# PCF8574T.net
KiCad netlist of a schematic drawn in EAGLE
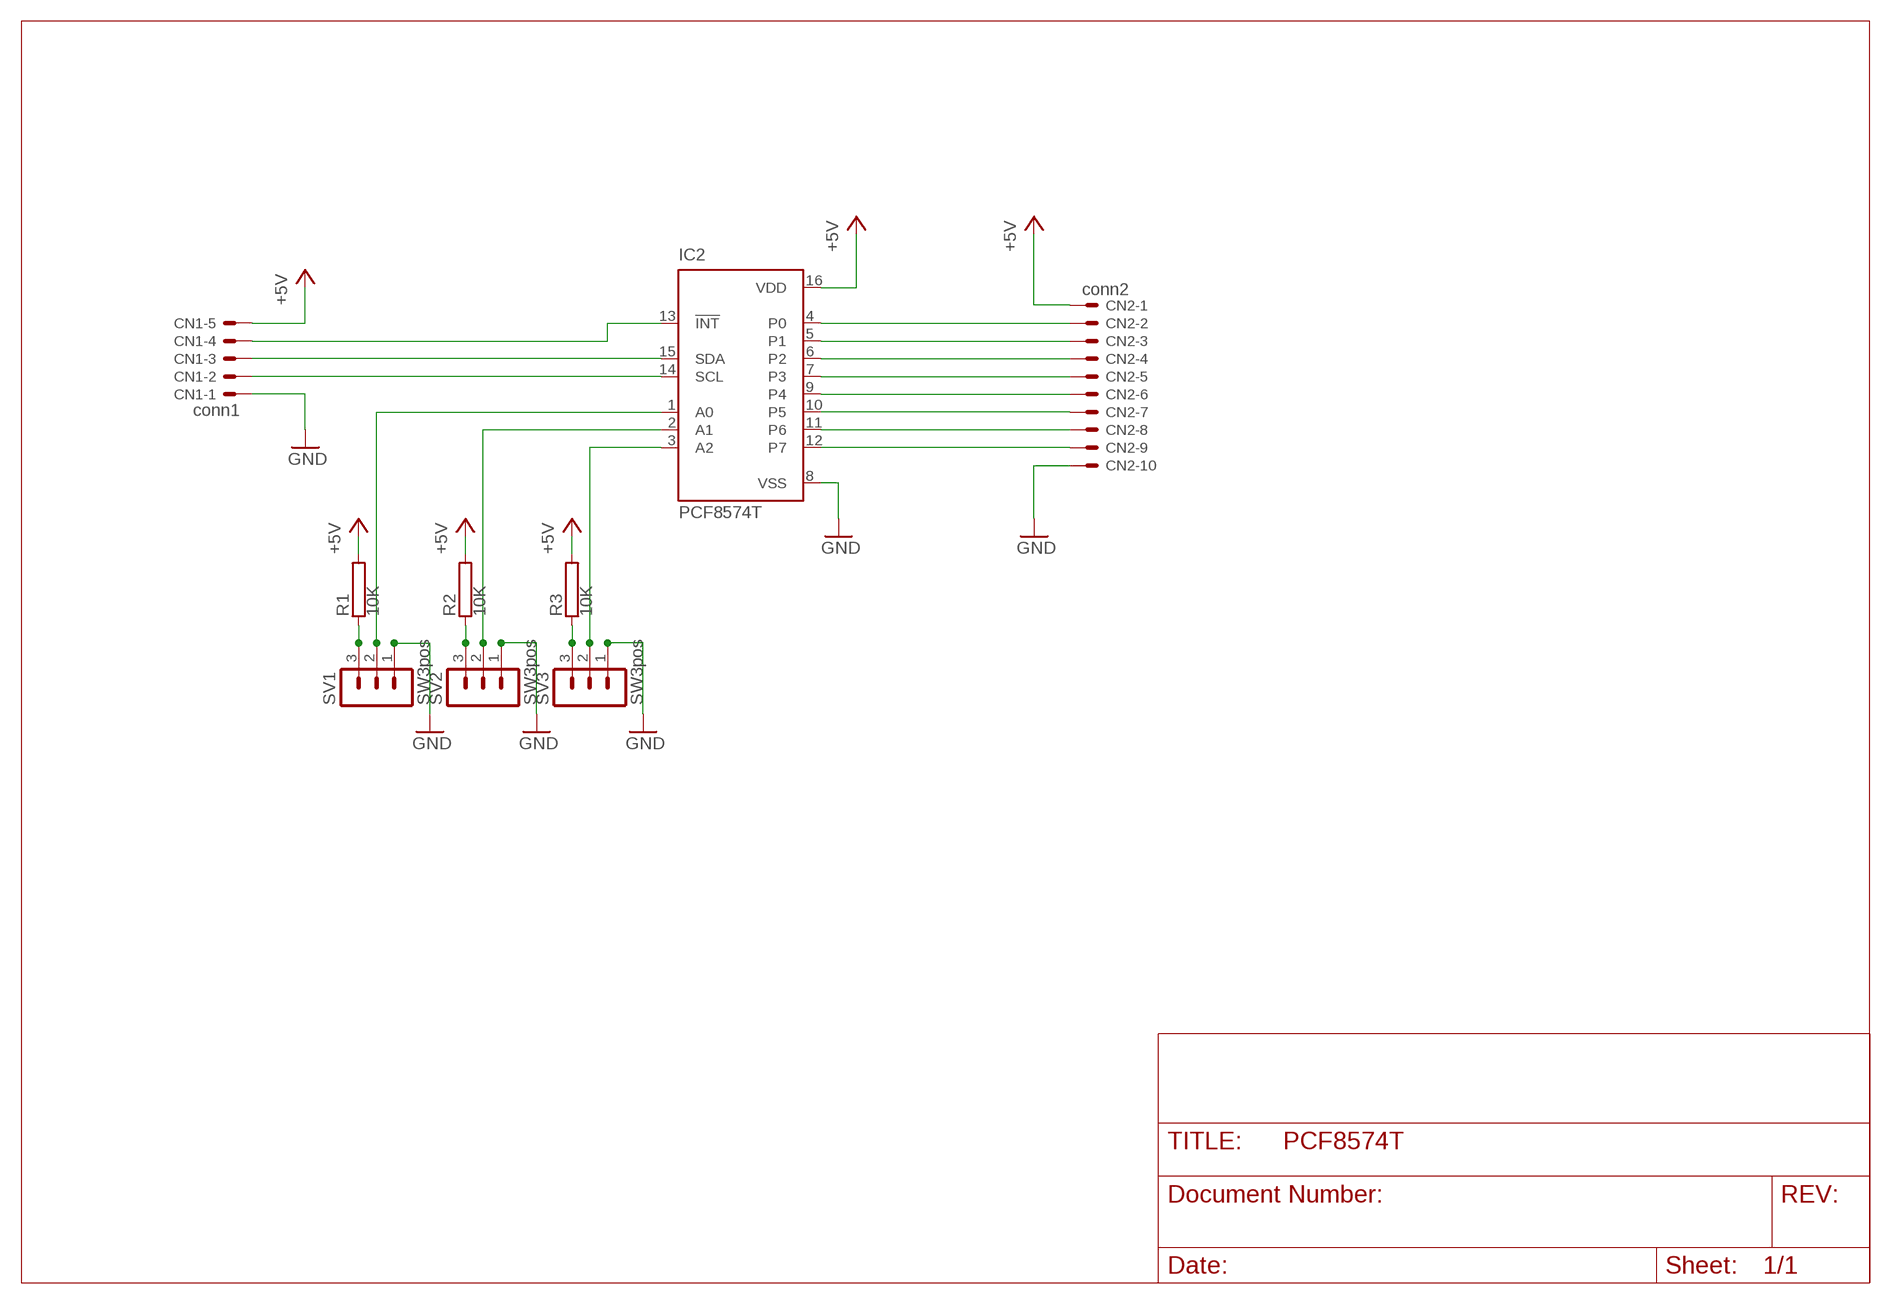
[diagram p0: schematic, sheet 1]

(export (version "E")
  (design (tool "Eeschema 10.0.6"))
  (components
    (comp (ref "CN1")
      (value "conn1")
      (footprint "eagle-import:22-23-2051")
      (fields (field (name "MF") "MOLEX") (field (name "MPN") "22-23-2051"))
      (libsource (lib "eagle-import") (part "22-23-2051"))
    )
    (comp (ref "CN2")
      (value "conn2")
      (footprint "eagle-import:22-23-2101")
      (fields (field (name "MF") "MOLEX") (field (name "MPN") "22-23-2101"))
      (libsource (lib "eagle-import") (part "22-23-2101"))
    )
    (comp (ref "IC2")
      (value "PCF8574T")
      (footprint "eagle-import:SO16W")
      (fields (field (name "MPN") "PCF8574T/3,512"))
      (libsource (lib "eagle-import") (part "PCF8574T"))
    )
    (comp (ref "R1")
      (value "10K")
      (footprint "eagle-import:HPS58")
      (libsource (lib "eagle-import") (part "RHPS58"))
    )
    (comp (ref "R2")
      (value "10K")
      (footprint "eagle-import:HPS58")
      (libsource (lib "eagle-import") (part "RHPS58"))
    )
    (comp (ref "R3")
      (value "10K")
      (footprint "eagle-import:HPS58")
      (libsource (lib "eagle-import") (part "RHPS58"))
    )
    (comp (ref "SV1")
      (value "SW3pos")
      (footprint "eagle-import:MA03-1")
      (libsource (lib "eagle-import") (part "MA03-1"))
    )
    (comp (ref "SV2")
      (value "SW3pos")
      (footprint "eagle-import:MA03-1")
      (libsource (lib "eagle-import") (part "MA03-1"))
    )
    (comp (ref "SV3")
      (value "SW3pos")
      (footprint "eagle-import:MA03-1")
      (libsource (lib "eagle-import") (part "MA03-1"))
    )
  )
  (nets
    (net (code "1") (name "+5V") (class "Default")
      (node (ref "CN1") (pin "5") (pinfunction "S_5") (pintype "passive"))
      (node (ref "CN2") (pin "1") (pinfunction "S_1") (pintype "passive"))
      (node (ref "IC2") (pin "16") (pinfunction "VDD_16") (pintype "power_in"))
      (node (ref "R1") (pin "2") (pinfunction "2_2") (pintype "passive"))
      (node (ref "R2") (pin "2") (pinfunction "2_2") (pintype "passive"))
      (node (ref "R3") (pin "2") (pinfunction "2_2") (pintype "passive"))
    )
    (net (code "2") (name "GND") (class "Default")
      (node (ref "CN1") (pin "1") (pinfunction "S_1") (pintype "passive"))
      (node (ref "CN2") (pin "10") (pinfunction "S_10") (pintype "passive"))
      (node (ref "IC2") (pin "8") (pinfunction "VSS_8") (pintype "power_in"))
      (node (ref "SV1") (pin "1") (pinfunction "1_1") (pintype "passive"))
      (node (ref "SV2") (pin "1") (pinfunction "1_1") (pintype "passive"))
      (node (ref "SV3") (pin "1") (pinfunction "1_1") (pintype "passive"))
    )
    (net (code "3") (name "Net-(CN1B-S)") (class "Default")
      (node (ref "CN1") (pin "2") (pinfunction "S_2") (pintype "passive"))
      (node (ref "IC2") (pin "14") (pinfunction "SCL_14") (pintype "input"))
    )
    (net (code "4") (name "Net-(CN1C-S)") (class "Default")
      (node (ref "CN1") (pin "3") (pinfunction "S_3") (pintype "passive"))
      (node (ref "IC2") (pin "15") (pinfunction "SDA_15") (pintype "bidirectional"))
    )
    (net (code "5") (name "Net-(CN1D-S)") (class "Default")
      (node (ref "CN1") (pin "4") (pinfunction "S_4") (pintype "passive"))
      (node (ref "IC2") (pin "13") (pinfunction "~{INT}_13") (pintype "output"))
    )
    (net (code "6") (name "Net-(CN2C-S)") (class "Default")
      (node (ref "CN2") (pin "2") (pinfunction "S_2") (pintype "passive"))
      (node (ref "IC2") (pin "4") (pinfunction "P0_4") (pintype "bidirectional"))
    )
    (net (code "7") (name "Net-(CN2D-S)") (class "Default")
      (node (ref "CN2") (pin "3") (pinfunction "S_3") (pintype "passive"))
      (node (ref "IC2") (pin "5") (pinfunction "P1_5") (pintype "bidirectional"))
    )
    (net (code "8") (name "Net-(CN2E-S)") (class "Default")
      (node (ref "CN2") (pin "4") (pinfunction "S_4") (pintype "passive"))
      (node (ref "IC2") (pin "6") (pinfunction "P2_6") (pintype "bidirectional"))
    )
    (net (code "9") (name "Net-(CN2F-S)") (class "Default")
      (node (ref "CN2") (pin "5") (pinfunction "S_5") (pintype "passive"))
      (node (ref "IC2") (pin "7") (pinfunction "P3_7") (pintype "bidirectional"))
    )
    (net (code "10") (name "Net-(CN2G-S)") (class "Default")
      (node (ref "CN2") (pin "6") (pinfunction "S_6") (pintype "passive"))
      (node (ref "IC2") (pin "9") (pinfunction "P4_9") (pintype "bidirectional"))
    )
    (net (code "11") (name "Net-(CN2H-S)") (class "Default")
      (node (ref "CN2") (pin "7") (pinfunction "S_7") (pintype "passive"))
      (node (ref "IC2") (pin "10") (pinfunction "P5_10") (pintype "bidirectional"))
    )
    (net (code "12") (name "Net-(CN2I-S)") (class "Default")
      (node (ref "CN2") (pin "8") (pinfunction "S_8") (pintype "passive"))
      (node (ref "IC2") (pin "11") (pinfunction "P6_11") (pintype "bidirectional"))
    )
    (net (code "13") (name "Net-(CN2J-S)") (class "Default")
      (node (ref "CN2") (pin "9") (pinfunction "S_9") (pintype "passive"))
      (node (ref "IC2") (pin "12") (pinfunction "P7_12") (pintype "bidirectional"))
    )
    (net (code "14") (name "Net-(IC2-A0)") (class "Default")
      (node (ref "IC2") (pin "1") (pinfunction "A0_1") (pintype "input"))
      (node (ref "SV1") (pin "2") (pinfunction "2_2") (pintype "passive"))
    )
    (net (code "15") (name "Net-(IC2-A1)") (class "Default")
      (node (ref "IC2") (pin "2") (pinfunction "A1_2") (pintype "input"))
      (node (ref "SV2") (pin "2") (pinfunction "2_2") (pintype "passive"))
    )
    (net (code "16") (name "Net-(IC2-A2)") (class "Default")
      (node (ref "IC2") (pin "3") (pinfunction "A2_3") (pintype "input"))
      (node (ref "SV3") (pin "2") (pinfunction "2_2") (pintype "passive"))
    )
    (net (code "17") (name "Net-(R1-Pad1)") (class "Default")
      (node (ref "R1") (pin "1") (pinfunction "1_1") (pintype "passive"))
      (node (ref "SV1") (pin "3") (pinfunction "3_3") (pintype "passive"))
    )
    (net (code "18") (name "Net-(R2-Pad1)") (class "Default")
      (node (ref "R2") (pin "1") (pinfunction "1_1") (pintype "passive"))
      (node (ref "SV2") (pin "3") (pinfunction "3_3") (pintype "passive"))
    )
    (net (code "19") (name "Net-(R3-Pad1)") (class "Default")
      (node (ref "R3") (pin "1") (pinfunction "1_1") (pintype "passive"))
      (node (ref "SV3") (pin "3") (pinfunction "3_3") (pintype "passive"))
    )
  )
)
